# eps_bb2.net
KiCad netlist of a schematic drawn in Altium Designer
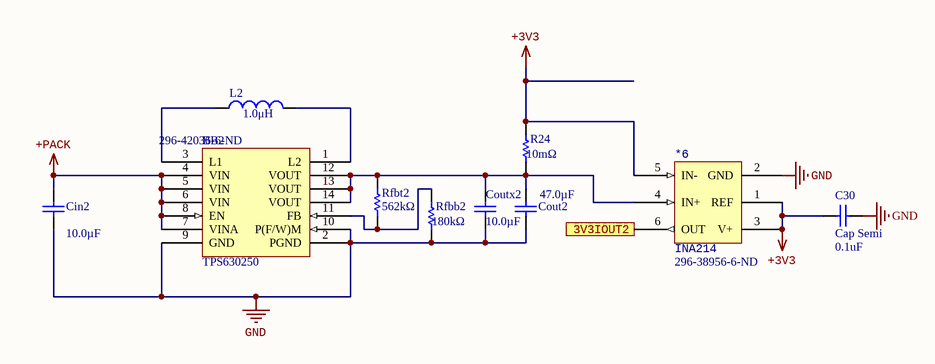
[diagram p0: eps_bb2.SchDoc]

(export (version "E")
  (design (tool "Eeschema 10.0.6"))
  (components
    (comp (ref "*6")
      (value "INA214")
      (footprint "SOT65P210X110-6N")
      (description "Current monitor")
      (fields (field (name "SUPPLIER PART NUMBER 1") "296-38956-6-ND"))
      (libsource (lib "heron-general") (part "INA214"))
    )
    (comp (ref "BB2")
      (value "TPS630250")
      (footprint "RNC0014A")
      (description "Buck-boost converter")
      (fields (field (name "SUPPLIER PART NUMBER 1") "296-42036-6-ND"))
      (libsource (lib "heron-general") (part "TPS630250"))
    )
    (comp (ref "C30")
      (value "Cap Semi")
      (footprint "1608[0603]")
      (description "Capacitor (Semiconductor SIM Model)")
      (fields (field (name "ALTIUM_VALUE") "0.1uF") (field (name "PUBLISHER") "Altium Limited"))
      (libsource (lib "Miscellaneous Devices") (part "Cap Semi"))
    )
    (comp (ref "Cin2")
      (value "10.0µF")
      (footprint "1608[0603]")
      (description "Capacitor")
      (fields (field (name "Comment") "Cap") (field (name "PUBLISHER") "Altium Limited"))
      (libsource (lib "Miscellaneous Devices") (part "Cap"))
    )
    (comp (ref "Cout2")
      (value "47.0µF")
      (footprint "1608[0603]")
      (description "Capacitor")
      (fields (field (name "Comment") "Cap") (field (name "PUBLISHER") "Altium Limited"))
      (libsource (lib "Miscellaneous Devices") (part "Cap"))
    )
    (comp (ref "Coutx2")
      (value "10.0µF")
      (footprint "1608[0603]")
      (description "Capacitor")
      (fields (field (name "Comment") "Cap") (field (name "PUBLISHER") "Altium Limited"))
      (libsource (lib "Miscellaneous Devices") (part "Cap"))
    )
    (comp (ref "L2")
      (value "1.0μH")
      (footprint "1608[0603]")
      (description "Inductor")
      (fields (field (name "PUBLISHER") "Altium Limited"))
      (libsource (lib "Miscellaneous Devices") (part "Inductor"))
    )
    (comp (ref "R24")
      (value "10mΩ")
      (footprint "1608[0603]")
      (description "Resistor")
      (fields (field (name "Comment") "Res1") (field (name "PUBLISHER") "Altium Limited"))
      (libsource (lib "Miscellaneous Devices") (part "Res1"))
    )
    (comp (ref "Rfbb2")
      (value "180kΩ")
      (footprint "1608[0603]")
      (description "Resistor")
      (fields (field (name "Comment") "Res1") (field (name "PUBLISHER") "Altium Limited"))
      (libsource (lib "Miscellaneous Devices") (part "Res1"))
    )
    (comp (ref "Rfbt2")
      (value "562kΩ")
      (footprint "1608[0603]")
      (description "Resistor")
      (fields (field (name "Comment") "Rfbt1") (field (name "PUBLISHER") "Altium Limited"))
      (libsource (lib "Miscellaneous Devices") (part "Res1"))
    )
  )
  (nets
    (net (code "1") (name "+3V3") (class "Default")
      (node (ref "*6") (pin "1") (pinfunction "REF_1") (pintype "passive"))
      (node (ref "*6") (pin "3") (pinfunction "V+_3") (pintype "power_in"))
      (node (ref "*6") (pin "5") (pinfunction "IN-_5") (pintype "input"))
      (node (ref "C30") (pin "2") (pinfunction "2_2") (pintype "passive"))
      (node (ref "R24") (pin "2") (pinfunction "2_2") (pintype "passive"))
    )
    (net (code "2") (name "+PACK") (class "Default")
      (node (ref "BB2") (pin "4") (pinfunction "VIN_4") (pintype "power_in"))
      (node (ref "BB2") (pin "5") (pinfunction "VIN_5") (pintype "power_in"))
      (node (ref "BB2") (pin "6") (pinfunction "VIN_6") (pintype "power_in"))
      (node (ref "BB2") (pin "7") (pinfunction "VINA_7") (pintype "power_in"))
      (node (ref "BB2") (pin "8") (pinfunction "EN_8") (pintype "input"))
      (node (ref "Cin2") (pin "2") (pinfunction "2_2") (pintype "passive"))
    )
    (net (code "3") (name "/3V3IOUT2") (class "Default")
      (node (ref "*6") (pin "6") (pinfunction "OUT_6") (pintype "output"))
    )
    (net (code "4") (name "GND") (class "Default")
      (node (ref "*6") (pin "2") (pinfunction "GND_2") (pintype "power_in"))
      (node (ref "BB2") (pin "10") (pinfunction "P(F/W)M_10") (pintype "input"))
      (node (ref "BB2") (pin "2") (pinfunction "PGND_2") (pintype "power_in"))
      (node (ref "BB2") (pin "9") (pinfunction "GND_9") (pintype "power_in"))
      (node (ref "C30") (pin "1") (pinfunction "1_1") (pintype "passive"))
      (node (ref "Cin2") (pin "1") (pinfunction "1_1") (pintype "passive"))
      (node (ref "Cout2") (pin "1") (pinfunction "1_1") (pintype "passive"))
      (node (ref "Coutx2") (pin "1") (pinfunction "1_1") (pintype "passive"))
      (node (ref "Rfbb2") (pin "1") (pinfunction "1_1") (pintype "passive"))
    )
    (net (code "5") (name "Net-(*6-IN+)") (class "Default")
      (node (ref "*6") (pin "4") (pinfunction "IN+_4") (pintype "input"))
      (node (ref "BB2") (pin "12") (pinfunction "VOUT_12") (pintype "passive"))
      (node (ref "BB2") (pin "13") (pinfunction "VOUT_13") (pintype "passive"))
      (node (ref "BB2") (pin "14") (pinfunction "VOUT_14") (pintype "passive"))
      (node (ref "Cout2") (pin "2") (pinfunction "2_2") (pintype "passive"))
      (node (ref "Coutx2") (pin "2") (pinfunction "2_2") (pintype "passive"))
      (node (ref "R24") (pin "1") (pinfunction "1_1") (pintype "passive"))
      (node (ref "Rfbt2") (pin "1") (pinfunction "1_1") (pintype "passive"))
    )
    (net (code "6") (name "Net-(BB2-FB)") (class "Default")
      (node (ref "BB2") (pin "11") (pinfunction "FB_11") (pintype "input"))
      (node (ref "Rfbb2") (pin "2") (pinfunction "2_2") (pintype "passive"))
      (node (ref "Rfbt2") (pin "2") (pinfunction "2_2") (pintype "passive"))
    )
    (net (code "7") (name "Net-(BB2-L1)") (class "Default")
      (node (ref "BB2") (pin "3") (pinfunction "L1_3") (pintype "power_in"))
      (node (ref "L2") (pin "1") (pinfunction "1_1") (pintype "passive"))
    )
    (net (code "8") (name "Net-(BB2-L2)") (class "Default")
      (node (ref "BB2") (pin "1") (pinfunction "L2_1") (pintype "power_in"))
      (node (ref "L2") (pin "2") (pinfunction "2_2") (pintype "passive"))
    )
  )
)
